# rpi.net
KiCad netlist of a schematic drawn in EAGLE
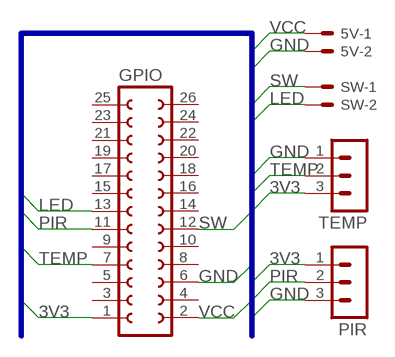
[diagram p0: schematic, sheet 1]

(export (version "E")
  (design (tool "Eeschema 10.0.6"))
  (components
    (comp (ref "5V")
      (value "22-23-2021")
      (footprint "eagle-import:22-23-2021")
      (fields (field (name "MF") "MOLEX"))
      (libsource (lib "eagle-import") (part "22-23-2021"))
    )
    (comp (ref "GPIO")
      (value "FE13-2")
      (footprint "eagle-import:FE13-2")
      (libsource (lib "eagle-import") (part "FE13-2"))
    )
    (comp (ref "PIR")
      (value "MA03-1")
      (footprint "eagle-import:MA03-1")
      (libsource (lib "eagle-import") (part "MA03-1"))
    )
    (comp (ref "SW")
      (value "22-23-2021")
      (footprint "eagle-import:22-23-2021")
      (fields (field (name "MF") "MOLEX"))
      (libsource (lib "eagle-import") (part "22-23-2021"))
    )
    (comp (ref "TEMP")
      (value "MA03-1")
      (footprint "eagle-import:MA03-1")
      (libsource (lib "eagle-import") (part "MA03-1"))
    )
  )
  (nets
    (net (code "1") (name "/3V3") (class "Default")
      (node (ref "GPIO") (pin "1") (pinfunction "1_1") (pintype "passive"))
      (node (ref "PIR") (pin "1") (pinfunction "1_1") (pintype "passive"))
      (node (ref "TEMP") (pin "3") (pinfunction "3_3") (pintype "passive"))
    )
    (net (code "2") (name "/GND") (class "Default")
      (node (ref "5V") (pin "2") (pinfunction "S_2") (pintype "passive"))
      (node (ref "GPIO") (pin "6") (pinfunction "6_6") (pintype "passive"))
      (node (ref "PIR") (pin "3") (pinfunction "3_3") (pintype "passive"))
      (node (ref "TEMP") (pin "1") (pinfunction "1_1") (pintype "passive"))
    )
    (net (code "3") (name "/LED") (class "Default")
      (node (ref "GPIO") (pin "13") (pinfunction "13_13") (pintype "passive"))
      (node (ref "SW") (pin "2") (pinfunction "S_2") (pintype "passive"))
    )
    (net (code "4") (name "/PIR") (class "Default")
      (node (ref "GPIO") (pin "11") (pinfunction "11_11") (pintype "passive"))
      (node (ref "PIR") (pin "2") (pinfunction "2_2") (pintype "passive"))
    )
    (net (code "5") (name "/SW") (class "Default")
      (node (ref "GPIO") (pin "12") (pinfunction "12_12") (pintype "passive"))
      (node (ref "SW") (pin "1") (pinfunction "S_1") (pintype "passive"))
    )
    (net (code "6") (name "/TEMP") (class "Default")
      (node (ref "GPIO") (pin "7") (pinfunction "7_7") (pintype "passive"))
      (node (ref "TEMP") (pin "2") (pinfunction "2_2") (pintype "passive"))
    )
    (net (code "7") (name "/VCC") (class "Default")
      (node (ref "5V") (pin "1") (pinfunction "S_1") (pintype "passive"))
      (node (ref "GPIO") (pin "2") (pinfunction "2_2") (pintype "passive"))
    )
    (net (code "8") (name "unconnected-(GPIO-Pad3)") (class "Default")
      (node (ref "GPIO") (pin "3") (pinfunction "3_3") (pintype "passive"))
    )
    (net (code "9") (name "unconnected-(GPIO-Pad4)") (class "Default")
      (node (ref "GPIO") (pin "4") (pinfunction "4_4") (pintype "passive"))
    )
    (net (code "10") (name "unconnected-(GPIO-Pad5)") (class "Default")
      (node (ref "GPIO") (pin "5") (pinfunction "5_5") (pintype "passive"))
    )
    (net (code "11") (name "unconnected-(GPIO-Pad8)") (class "Default")
      (node (ref "GPIO") (pin "8") (pinfunction "8_8") (pintype "passive"))
    )
    (net (code "12") (name "unconnected-(GPIO-Pad9)") (class "Default")
      (node (ref "GPIO") (pin "9") (pinfunction "9_9") (pintype "passive"))
    )
    (net (code "13") (name "unconnected-(GPIO-Pad10)") (class "Default")
      (node (ref "GPIO") (pin "10") (pinfunction "10_10") (pintype "passive"))
    )
    (net (code "14") (name "unconnected-(GPIO-Pad14)") (class "Default")
      (node (ref "GPIO") (pin "14") (pinfunction "14_14") (pintype "passive"))
    )
    (net (code "15") (name "unconnected-(GPIO-Pad15)") (class "Default")
      (node (ref "GPIO") (pin "15") (pinfunction "15_15") (pintype "passive"))
    )
    (net (code "16") (name "unconnected-(GPIO-Pad16)") (class "Default")
      (node (ref "GPIO") (pin "16") (pinfunction "16_16") (pintype "passive"))
    )
    (net (code "17") (name "unconnected-(GPIO-Pad17)") (class "Default")
      (node (ref "GPIO") (pin "17") (pinfunction "17_17") (pintype "passive"))
    )
    (net (code "18") (name "unconnected-(GPIO-Pad18)") (class "Default")
      (node (ref "GPIO") (pin "18") (pinfunction "18_18") (pintype "passive"))
    )
    (net (code "19") (name "unconnected-(GPIO-Pad19)") (class "Default")
      (node (ref "GPIO") (pin "19") (pinfunction "19_19") (pintype "passive"))
    )
    (net (code "20") (name "unconnected-(GPIO-Pad20)") (class "Default")
      (node (ref "GPIO") (pin "20") (pinfunction "20_20") (pintype "passive"))
    )
    (net (code "21") (name "unconnected-(GPIO-Pad21)") (class "Default")
      (node (ref "GPIO") (pin "21") (pinfunction "21_21") (pintype "passive"))
    )
    (net (code "22") (name "unconnected-(GPIO-Pad22)") (class "Default")
      (node (ref "GPIO") (pin "22") (pinfunction "22_22") (pintype "passive"))
    )
    (net (code "23") (name "unconnected-(GPIO-Pad23)") (class "Default")
      (node (ref "GPIO") (pin "23") (pinfunction "23_23") (pintype "passive"))
    )
    (net (code "24") (name "unconnected-(GPIO-Pad24)") (class "Default")
      (node (ref "GPIO") (pin "24") (pinfunction "24_24") (pintype "passive"))
    )
    (net (code "25") (name "unconnected-(GPIO-Pad25)") (class "Default")
      (node (ref "GPIO") (pin "25") (pinfunction "25_25") (pintype "passive"))
    )
    (net (code "26") (name "unconnected-(GPIO-Pad26)") (class "Default")
      (node (ref "GPIO") (pin "26") (pinfunction "26_26") (pintype "passive"))
    )
  )
)
